# RS422_driver.net
KiCad netlist of a schematic drawn in Altium Designer
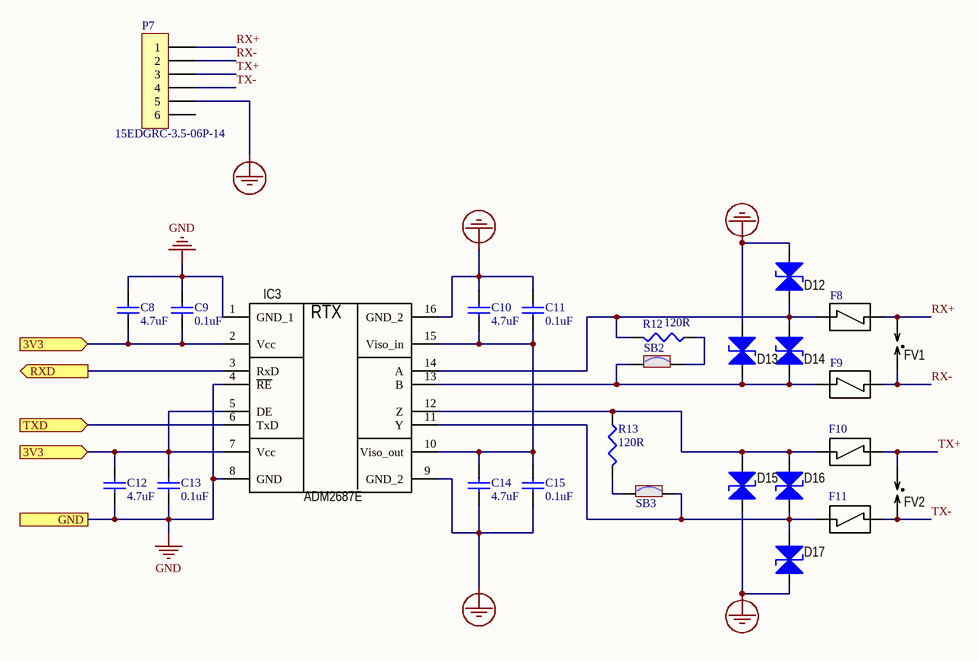
[diagram p0: RS422_driver.SchDoc]

(export (version "E")
  (design (tool "Eeschema 10.0.6"))
  (components
    (comp (ref "C8")
      (value "4.7uF")
      (footprint "C1608-0603")
      (description "Керамическийконденсатор")
      (libsource (lib "db") (part "Cap"))
    )
    (comp (ref "C9")
      (value "0.1uF")
      (footprint "C1608-0603")
      (description "Керамическийконденсатор")
      (libsource (lib "db") (part "Cap"))
    )
    (comp (ref "C10")
      (value "4.7uF")
      (footprint "C1608-0603")
      (description "Керамическийконденсатор")
      (libsource (lib "db") (part "Cap"))
    )
    (comp (ref "C11")
      (value "0.1uF")
      (footprint "C1608-0603")
      (description "Керамическийконденсатор")
      (libsource (lib "db") (part "Cap"))
    )
    (comp (ref "C12")
      (value "4.7uF")
      (footprint "C1608-0603")
      (description "Керамическийконденсатор")
      (libsource (lib "db") (part "Cap"))
    )
    (comp (ref "C13")
      (value "0.1uF")
      (footprint "C1608-0603")
      (description "Керамическийконденсатор")
      (libsource (lib "db") (part "Cap"))
    )
    (comp (ref "C14")
      (value "4.7uF")
      (footprint "C1608-0603")
      (description "Керамическийконденсатор")
      (libsource (lib "db") (part "Cap"))
    )
    (comp (ref "C15")
      (value "0.1uF")
      (footprint "C1608-0603")
      (description "Керамическийконденсатор")
      (libsource (lib "db") (part "Cap"))
    )
    (comp (ref "D12")
      (value "SMBJ5.0CA")
      (footprint "SMB_H")
      (description "Супрессор двунаправленный")
      (libsource (lib "db") (part "SMBJ_CА"))
    )
    (comp (ref "D13")
      (value "SMBJ5.0CA")
      (footprint "SMB_H")
      (description "Супрессор двунаправленный")
      (libsource (lib "db") (part "SMBJ_CА"))
    )
    (comp (ref "D14")
      (value "SMBJ5.0CA")
      (footprint "SMB_H")
      (description "Супрессор двунаправленный")
      (libsource (lib "db") (part "SMBJ_CА"))
    )
    (comp (ref "D15")
      (value "SMBJ5.0CA")
      (footprint "SMB_H")
      (description "Супрессор двунаправленный")
      (libsource (lib "db") (part "SMBJ_CА"))
    )
    (comp (ref "D16")
      (value "SMBJ5.0CA")
      (footprint "SMB_H")
      (description "Супрессор двунаправленный")
      (libsource (lib "db") (part "SMBJ_CА"))
    )
    (comp (ref "D17")
      (value "SMBJ5.0CA")
      (footprint "SMB_H")
      (description "Супрессор двунаправленный")
      (libsource (lib "db") (part "SMBJ_CА"))
    )
    (comp (ref "F8")
      (value "TBU-CA065-200-WH")
      (footprint "TBU_CA")
      (description "Самовосстанавливающийся предохранитель")
      (libsource (lib "db") (part "TBU-CA"))
    )
    (comp (ref "F9")
      (value "TBU-CA065-200-WH")
      (footprint "TBU_CA")
      (description "Самовосстанавливающийся предохранитель")
      (libsource (lib "db") (part "TBU-CA"))
    )
    (comp (ref "F10")
      (value "TBU-CA065-200-WH")
      (footprint "TBU_CA")
      (description "Самовосстанавливающийся предохранитель")
      (libsource (lib "db") (part "TBU-CA"))
    )
    (comp (ref "F11")
      (value "TBU-CA065-200-WH")
      (footprint "TBU_CA")
      (description "Самовосстанавливающийся предохранитель")
      (libsource (lib "db") (part "TBU-CA"))
    )
    (comp (ref "FV1")
      (value "NS2R-75A1-M")
      (footprint "NS2R-xxx-x")
      (description "Газовый разрядник двухэлектродный")
      (libsource (lib "") (part "NS2R-xxx-x_1_1"))
    )
    (comp (ref "FV2")
      (value "NS2R-75A1-M")
      (footprint "NS2R-xxx-x")
      (description "Газовый разрядник двухэлектродный")
      (libsource (lib "db") (part "NS2R-xxx-x_1"))
    )
    (comp (ref "IC3")
      (value "ADM2687E")
      (footprint "SO16_WIDE(300mil)_13x10_H")
      (description "RS-485 Трансивер изолированный")
      (libsource (lib "db") (part "ADM2687E"))
    )
    (comp (ref "P7")
      (value "15EDGRC-3.5-06P-14")
      (footprint "15EDGRC-3.5-06P-14")
      (description "Разъем штыревой на плату (папа)")
      (libsource (lib "db") (part "15EDGRC-3.5-06P-14"))
    )
    (comp (ref "R12")
      (value "120R")
      (footprint "R1608-0603")
      (description "SMD резистор")
      (libsource (lib "db") (part "resistor"))
    )
    (comp (ref "R13")
      (value "120R")
      (footprint "R1608-0603")
      (description "SMD резистор")
      (libsource (lib "db") (part "resistor"))
    )
    (comp (ref "SB2")
      (value "~")
      (footprint "SOLDER-BRIDGE_R0603-0R")
      (description "Перемычка")
      (libsource (lib "") (part "SB_1"))
    )
    (comp (ref "SB3")
      (value "~")
      (footprint "SOLDER-BRIDGE_R0603-0R")
      (description "Перемычка")
      (libsource (lib "db") (part "SB"))
    )
  )
  (nets
    (net (code "1") (name "/3V3") (class "Default")
      (node (ref "C12") (pin "2") (pinfunction "2_2") (pintype "passive"))
      (node (ref "C13") (pin "2") (pinfunction "2_2") (pintype "passive"))
      (node (ref "C8") (pin "1") (pinfunction "1_1") (pintype "passive"))
      (node (ref "C9") (pin "1") (pinfunction "1_1") (pintype "passive"))
      (node (ref "IC3") (pin "2") (pinfunction "Vcc_2") (pintype "power_in"))
      (node (ref "IC3") (pin "5") (pinfunction "DE_5") (pintype "passive"))
      (node (ref "IC3") (pin "7") (pinfunction "Vcc_7") (pintype "passive"))
    )
    (net (code "2") (name "/RX+") (class "Default")
      (node (ref "F8") (pin "1") (pintype "passive"))
      (node (ref "FV1") (pin "2") (pinfunction "L_2") (pintype "passive"))
      (node (ref "P7") (pin "1") (pinfunction "1_1") (pintype "passive"))
    )
    (net (code "3") (name "/RX-") (class "Default")
      (node (ref "F9") (pin "1") (pintype "passive"))
      (node (ref "FV1") (pin "1") (pinfunction "R_1") (pintype "passive"))
      (node (ref "P7") (pin "2") (pinfunction "2_2") (pintype "passive"))
    )
    (net (code "4") (name "/RXD") (class "Default")
      (node (ref "IC3") (pin "3") (pinfunction "RxD_3") (pintype "passive"))
    )
    (net (code "5") (name "/TX+") (class "Default")
      (node (ref "F10") (pin "1") (pintype "passive"))
      (node (ref "FV2") (pin "1") (pinfunction "R_1") (pintype "passive"))
      (node (ref "P7") (pin "3") (pinfunction "3_3") (pintype "passive"))
    )
    (net (code "6") (name "/TX-") (class "Default")
      (node (ref "F11") (pin "1") (pintype "passive"))
      (node (ref "FV2") (pin "2") (pinfunction "L_2") (pintype "passive"))
      (node (ref "P7") (pin "4") (pinfunction "4_4") (pintype "passive"))
    )
    (net (code "7") (name "/TXD") (class "Default")
      (node (ref "IC3") (pin "6") (pinfunction "TxD_6") (pintype "power_in"))
    )
    (net (code "8") (name "GND") (class "Default")
      (node (ref "C12") (pin "1") (pinfunction "1_1") (pintype "passive"))
      (node (ref "C13") (pin "1") (pinfunction "1_1") (pintype "passive"))
      (node (ref "C8") (pin "2") (pinfunction "2_2") (pintype "passive"))
      (node (ref "C9") (pin "2") (pinfunction "2_2") (pintype "passive"))
      (node (ref "IC3") (pin "1") (pinfunction "GND_1_1") (pintype "passive"))
      (node (ref "IC3") (pin "4") (pinfunction "~{RE}_4") (pintype "passive"))
      (node (ref "IC3") (pin "8") (pinfunction "GND_8") (pintype "passive"))
    )
    (net (code "9") (name "GND_line") (class "Default")
      (node (ref "C10") (pin "2") (pinfunction "2_2") (pintype "passive"))
      (node (ref "C11") (pin "2") (pinfunction "2_2") (pintype "passive"))
      (node (ref "C14") (pin "1") (pinfunction "1_1") (pintype "passive"))
      (node (ref "C15") (pin "1") (pinfunction "1_1") (pintype "passive"))
      (node (ref "D12") (pin "1") (pinfunction "K_1") (pintype "passive"))
      (node (ref "D13") (pin "1") (pinfunction "K_1") (pintype "passive"))
      (node (ref "D15") (pin "1") (pinfunction "K_1") (pintype "passive"))
      (node (ref "D17") (pin "1") (pinfunction "K_1") (pintype "passive"))
      (node (ref "IC3") (pin "16") (pinfunction "GND_2_16") (pintype "passive"))
      (node (ref "IC3") (pin "9") (pinfunction "GND_2_9") (pintype "passive"))
      (node (ref "P7") (pin "5") (pinfunction "5_5") (pintype "passive"))
    )
    (net (code "10") (name "Net-(D12-A)") (class "Default")
      (node (ref "D12") (pin "2") (pinfunction "A_2") (pintype "passive"))
      (node (ref "D14") (pin "1") (pinfunction "K_1") (pintype "passive"))
      (node (ref "F8") (pin "0") (pintype "passive"))
      (node (ref "IC3") (pin "14") (pinfunction "A_14") (pintype "power_in"))
      (node (ref "R12") (pin "2") (pinfunction "2_2") (pintype "passive"))
    )
    (net (code "11") (name "Net-(D13-A)") (class "Default")
      (node (ref "D13") (pin "2") (pinfunction "A_2") (pintype "passive"))
      (node (ref "D14") (pin "2") (pinfunction "A_2") (pintype "passive"))
      (node (ref "F9") (pin "0") (pintype "passive"))
      (node (ref "IC3") (pin "13") (pinfunction "B_13") (pintype "power_in"))
      (node (ref "SB2") (pin "1") (pinfunction "1_1") (pintype "passive"))
    )
    (net (code "12") (name "Net-(D15-A)") (class "Default")
      (node (ref "D15") (pin "2") (pinfunction "A_2") (pintype "passive"))
      (node (ref "D16") (pin "2") (pinfunction "A_2") (pintype "passive"))
      (node (ref "F10") (pin "0") (pintype "passive"))
      (node (ref "IC3") (pin "12") (pinfunction "Z_12") (pintype "power_in"))
      (node (ref "R13") (pin "2") (pinfunction "2_2") (pintype "passive"))
    )
    (net (code "13") (name "Net-(D16-K)") (class "Default")
      (node (ref "D16") (pin "1") (pinfunction "K_1") (pintype "passive"))
      (node (ref "D17") (pin "2") (pinfunction "A_2") (pintype "passive"))
      (node (ref "F11") (pin "0") (pintype "passive"))
      (node (ref "IC3") (pin "11") (pinfunction "Y_11") (pintype "power_in"))
      (node (ref "SB3") (pin "1") (pinfunction "1_1") (pintype "passive"))
    )
    (net (code "14") (name "Net-(IC3-Viso_in)") (class "Default")
      (node (ref "C10") (pin "1") (pinfunction "1_1") (pintype "passive"))
      (node (ref "C11") (pin "1") (pinfunction "1_1") (pintype "passive"))
      (node (ref "C14") (pin "2") (pinfunction "2_2") (pintype "passive"))
      (node (ref "C15") (pin "2") (pinfunction "2_2") (pintype "passive"))
      (node (ref "IC3") (pin "10") (pinfunction "Viso_out_10") (pintype "power_in"))
      (node (ref "IC3") (pin "15") (pinfunction "Viso_in_15") (pintype "power_in"))
    )
    (net (code "15") (name "Net-(R12-Pad1)") (class "Default")
      (node (ref "R12") (pin "1") (pinfunction "1_1") (pintype "passive"))
      (node (ref "SB2") (pin "2") (pinfunction "2_2") (pintype "passive"))
    )
    (net (code "16") (name "Net-(R13-Pad1)") (class "Default")
      (node (ref "R13") (pin "1") (pinfunction "1_1") (pintype "passive"))
      (node (ref "SB3") (pin "2") (pinfunction "2_2") (pintype "passive"))
    )
    (net (code "17") (name "unconnected-(P7-Pad6)") (class "Default")
      (node (ref "P7") (pin "6") (pinfunction "6_6") (pintype "passive"))
    )
  )
)
